# SCH_nodemcu_stepper_2023-12-21.net
KiCad netlist of a schematic drawn in EasyEDA
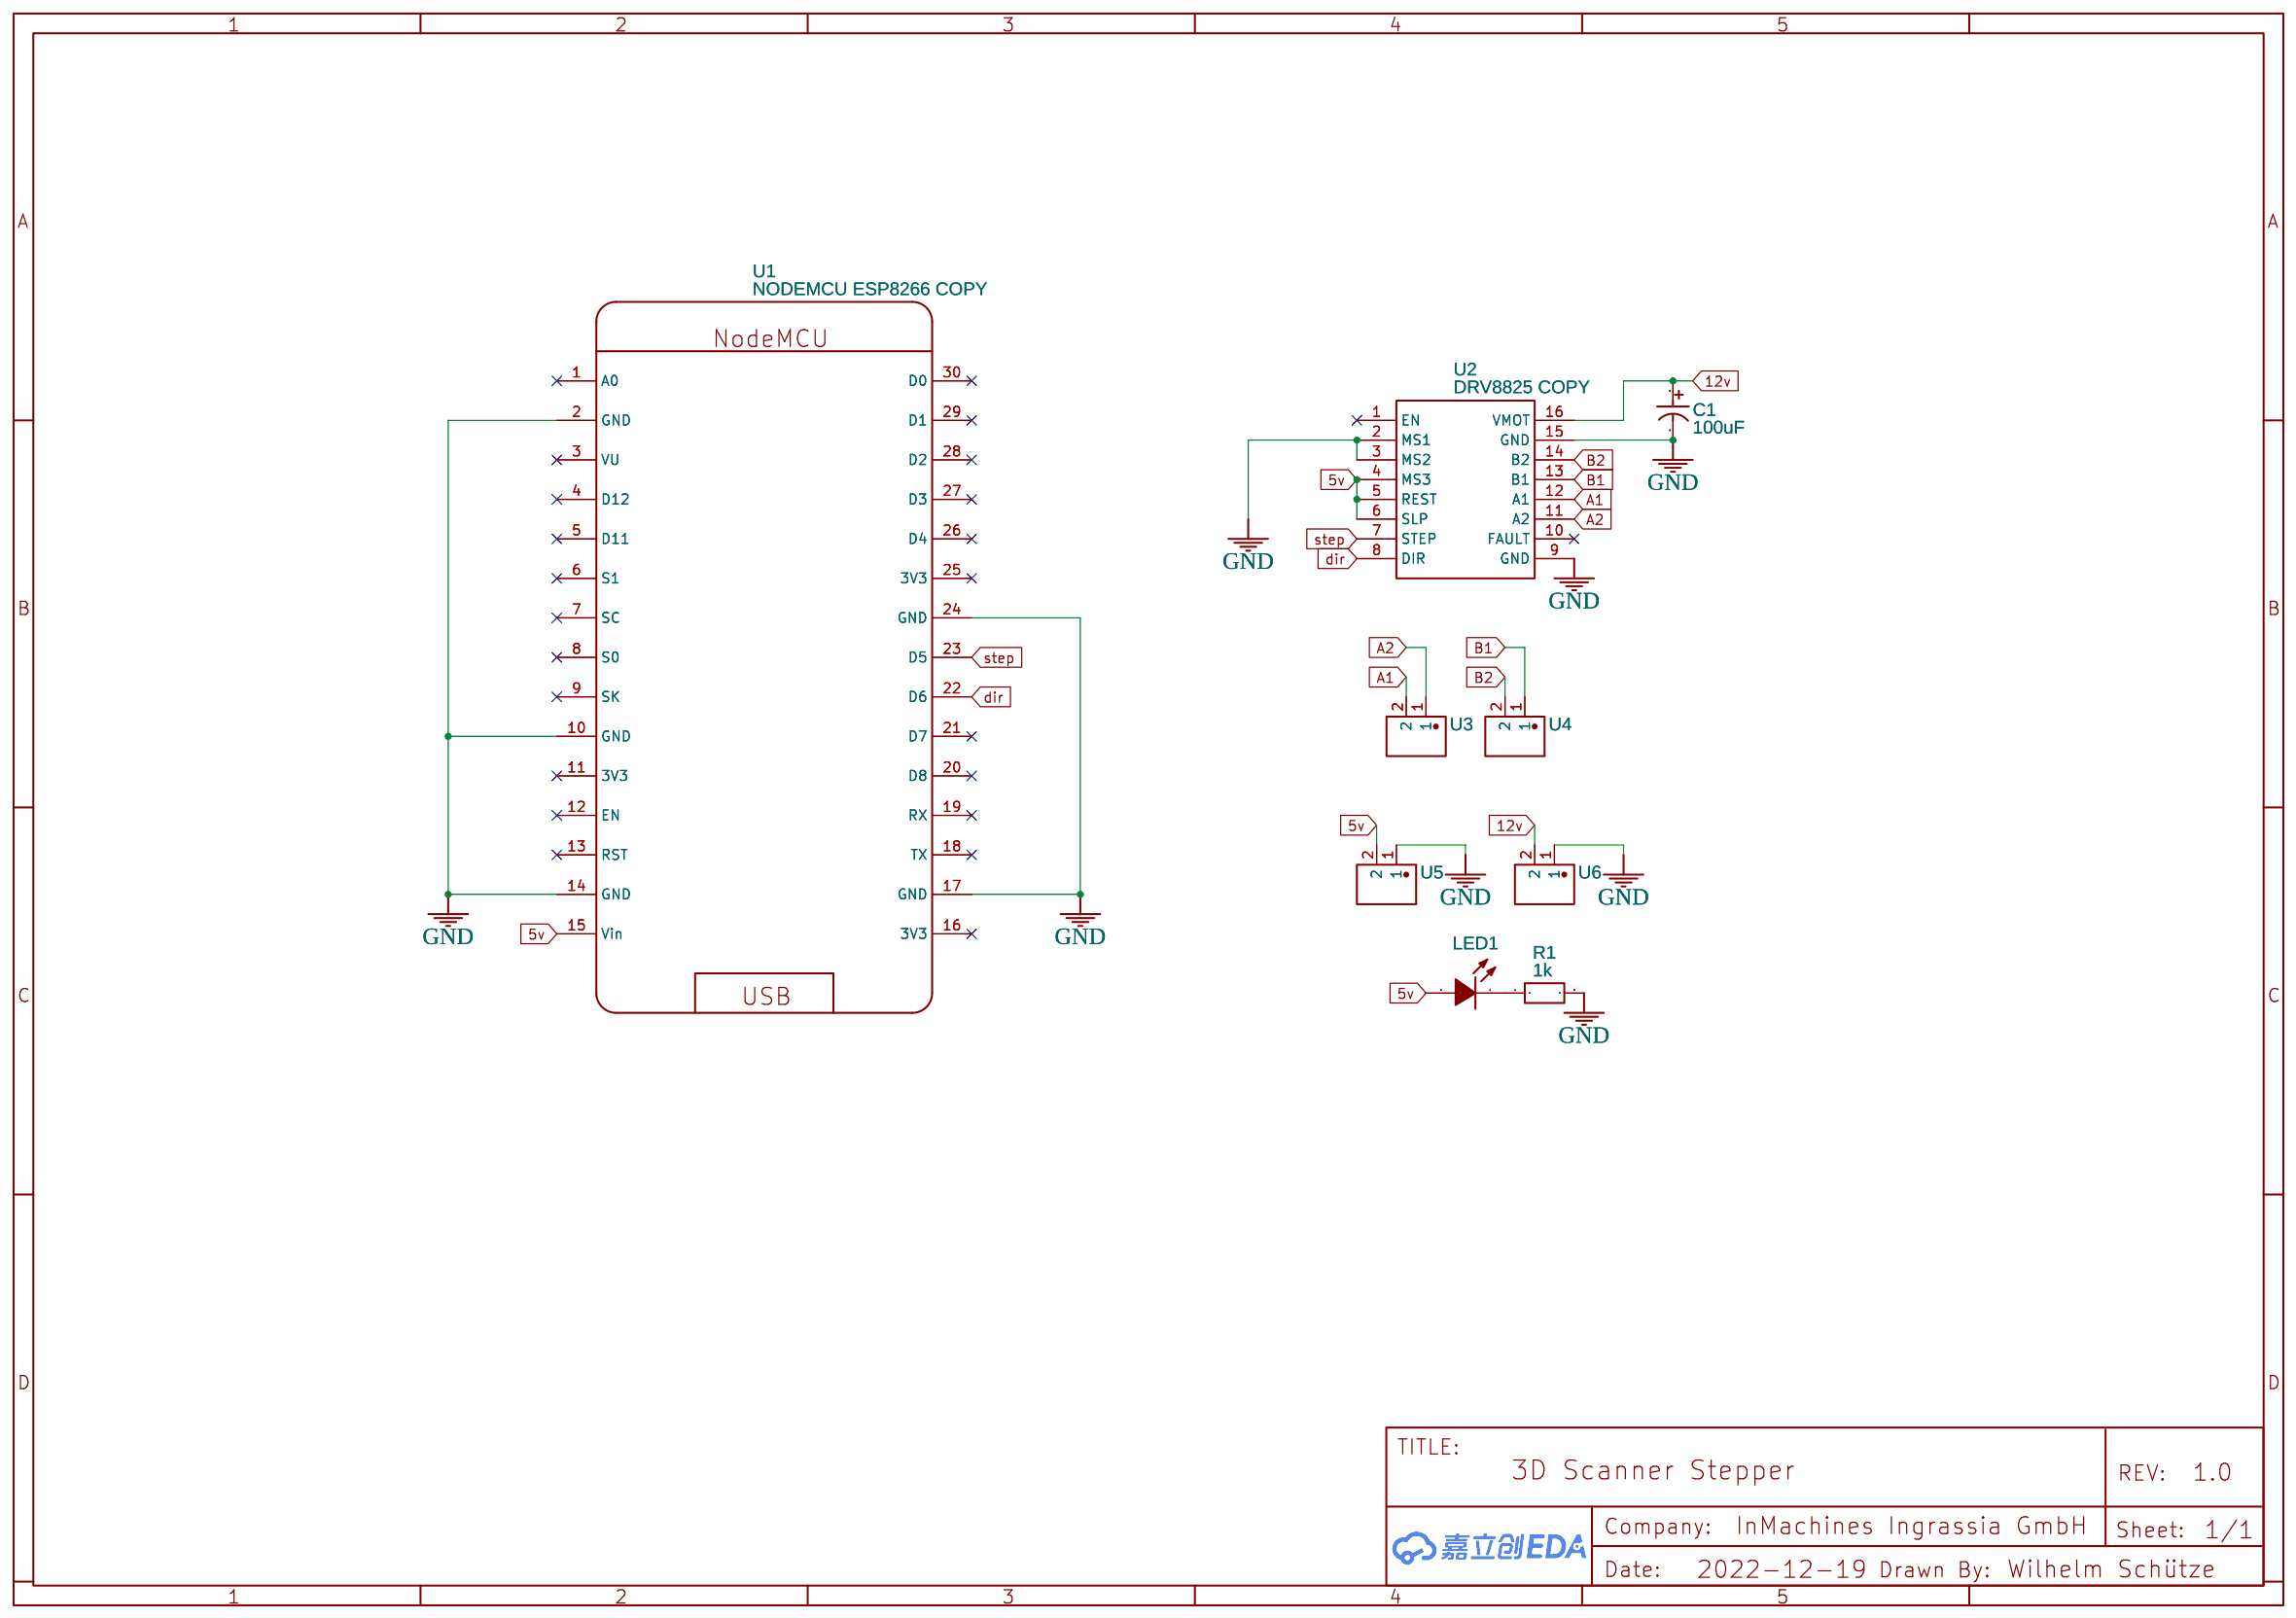
[diagram p0: schematic sheet]

(export (version "E")
  (design (tool "Eeschema 10.0.6"))
  (components
    (comp (ref "C1")
      (value "100uF")
      (fields (field (name "Manufacturer Part") "RVE1V101M0607") (field (name "Manufacturer") "ROQANG"))
      (libsource (lib "") (part "100UF-35V-KONDANSATOR"))
    )
    (comp (ref "LED1")
      (value "1206 LED Fab Lab UCAL")
      (fields (field (name "Manufacturer Part") "1206 LED") (field (name "Manufacturer") "KENTO"))
      (libsource (lib "") (part "1206 LED Fab Lab UCAL"))
    )
    (comp (ref "R1") (value "1k") (libsource (lib "") (part "R_1206_EU")))
    (comp (ref "U1") (value "NODEMCU ESP8266 COPY") (libsource (lib "") (part "NODEMCU ESP8266 COPY")))
    (comp (ref "U2") (value "DRV8825 COPY") (libsource (lib "") (part "DRV8825 COPY")))
    (comp (ref "U3")
      (value "DB128L-5.08-2P-GN-P")
      (fields (field (name "Manufacturer") "DIBO(地博电气)"))
      (libsource (lib "") (part "DB128L-5.08-2P-GN-P"))
    )
    (comp (ref "U4")
      (value "DB128L-5.08-2P-GN-P")
      (fields (field (name "Manufacturer") "DIBO(地博电气)"))
      (libsource (lib "") (part "DB128L-5.08-2P-GN-P"))
    )
    (comp (ref "U5")
      (value "DB128L-5.08-2P-GN-P")
      (fields (field (name "Manufacturer") "DIBO(地博电气)"))
      (libsource (lib "") (part "DB128L-5.08-2P-GN-P"))
    )
    (comp (ref "U6")
      (value "DB128L-5.08-2P-GN-P")
      (fields (field (name "Manufacturer") "DIBO(地博电气)"))
      (libsource (lib "") (part "DB128L-5.08-2P-GN-P"))
    )
  )
  (nets
    (net (code "1") (name "5v") (class "Default")
      (node (ref "LED1") (pin "2") (pinfunction "A_2") (pintype "unspecified"))
      (node (ref "U1") (pin "15") (pinfunction "Vin_15") (pintype "unspecified"))
      (node (ref "U2") (pin "4") (pinfunction "MS3_4") (pintype "unspecified"))
      (node (ref "U2") (pin "5") (pinfunction "REST_5") (pintype "unspecified"))
      (node (ref "U2") (pin "6") (pinfunction "SLP_6") (pintype "unspecified"))
      (node (ref "U5") (pin "2") (pinfunction "2_2") (pintype "unspecified"))
    )
    (net (code "2") (name "12v") (class "Default")
      (node (ref "C1") (pin "1") (pinfunction "1_1") (pintype "input"))
      (node (ref "U2") (pin "16") (pinfunction "VMOT_16") (pintype "unspecified"))
      (node (ref "U6") (pin "2") (pinfunction "2_2") (pintype "unspecified"))
    )
    (net (code "3") (name "A1") (class "Default")
      (node (ref "U2") (pin "12") (pinfunction "A1_12") (pintype "unspecified"))
      (node (ref "U3") (pin "2") (pinfunction "2_2") (pintype "unspecified"))
    )
    (net (code "4") (name "A2") (class "Default")
      (node (ref "U2") (pin "11") (pinfunction "A2_11") (pintype "unspecified"))
      (node (ref "U3") (pin "1") (pinfunction "1_1") (pintype "unspecified"))
    )
    (net (code "5") (name "B1") (class "Default")
      (node (ref "U2") (pin "13") (pinfunction "B1_13") (pintype "unspecified"))
      (node (ref "U4") (pin "1") (pinfunction "1_1") (pintype "unspecified"))
    )
    (net (code "6") (name "B2") (class "Default")
      (node (ref "U2") (pin "14") (pinfunction "B2_14") (pintype "unspecified"))
      (node (ref "U4") (pin "2") (pinfunction "2_2") (pintype "unspecified"))
    )
    (net (code "7") (name "GND") (class "Default")
      (node (ref "C1") (pin "2") (pinfunction "2_2") (pintype "input"))
      (node (ref "R1") (pin "2") (pinfunction "2_2") (pintype "unspecified"))
      (node (ref "U1") (pin "10") (pinfunction "GND_10") (pintype "unspecified"))
      (node (ref "U1") (pin "14") (pinfunction "GND_14") (pintype "unspecified"))
      (node (ref "U1") (pin "17") (pinfunction "GND_17") (pintype "unspecified"))
      (node (ref "U1") (pin "2") (pinfunction "GND_2") (pintype "unspecified"))
      (node (ref "U1") (pin "24") (pinfunction "GND_24") (pintype "unspecified"))
      (node (ref "U2") (pin "15") (pinfunction "GND_15") (pintype "unspecified"))
      (node (ref "U2") (pin "2") (pinfunction "MS1_2") (pintype "unspecified"))
      (node (ref "U2") (pin "3") (pinfunction "MS2_3") (pintype "unspecified"))
      (node (ref "U2") (pin "9") (pinfunction "GND_9") (pintype "unspecified"))
      (node (ref "U5") (pin "1") (pinfunction "1_1") (pintype "unspecified"))
      (node (ref "U6") (pin "1") (pinfunction "1_1") (pintype "unspecified"))
    )
    (net (code "8") (name "Net-(LED1-K)") (class "Default")
      (node (ref "LED1") (pin "1") (pinfunction "K_1") (pintype "unspecified"))
      (node (ref "R1") (pin "1") (pinfunction "1_1") (pintype "unspecified"))
    )
    (net (code "9") (name "dir") (class "Default")
      (node (ref "U1") (pin "22") (pinfunction "D6_22") (pintype "unspecified"))
      (node (ref "U2") (pin "8") (pinfunction "DIR_8") (pintype "unspecified"))
    )
    (net (code "10") (name "step") (class "Default")
      (node (ref "U1") (pin "23") (pinfunction "D5_23") (pintype "unspecified"))
      (node (ref "U2") (pin "7") (pinfunction "STEP_7") (pintype "unspecified"))
    )
    (net (code "11") (name "unconnected-(U1-3V3-Pad11)") (class "Default")
      (node (ref "U1") (pin "11") (pinfunction "3V3_11") (pintype "unspecified+no_connect"))
    )
    (net (code "12") (name "unconnected-(U1-3V3-Pad16)") (class "Default")
      (node (ref "U1") (pin "16") (pinfunction "3V3_16") (pintype "unspecified+no_connect"))
    )
    (net (code "13") (name "unconnected-(U1-3V3-Pad25)") (class "Default")
      (node (ref "U1") (pin "25") (pinfunction "3V3_25") (pintype "unspecified+no_connect"))
    )
    (net (code "14") (name "unconnected-(U1-A0-Pad1)") (class "Default")
      (node (ref "U1") (pin "1") (pinfunction "A0_1") (pintype "unspecified+no_connect"))
    )
    (net (code "15") (name "unconnected-(U1-D0-Pad30)") (class "Default")
      (node (ref "U1") (pin "30") (pinfunction "D0_30") (pintype "unspecified+no_connect"))
    )
    (net (code "16") (name "unconnected-(U1-D1-Pad29)") (class "Default")
      (node (ref "U1") (pin "29") (pinfunction "D1_29") (pintype "unspecified+no_connect"))
    )
    (net (code "17") (name "unconnected-(U1-D2-Pad28)") (class "Default")
      (node (ref "U1") (pin "28") (pinfunction "D2_28") (pintype "unspecified+no_connect"))
    )
    (net (code "18") (name "unconnected-(U1-D3-Pad27)") (class "Default")
      (node (ref "U1") (pin "27") (pinfunction "D3_27") (pintype "unspecified+no_connect"))
    )
    (net (code "19") (name "unconnected-(U1-D4-Pad26)") (class "Default")
      (node (ref "U1") (pin "26") (pinfunction "D4_26") (pintype "unspecified+no_connect"))
    )
    (net (code "20") (name "unconnected-(U1-D7-Pad21)") (class "Default")
      (node (ref "U1") (pin "21") (pinfunction "D7_21") (pintype "unspecified+no_connect"))
    )
    (net (code "21") (name "unconnected-(U1-D8-Pad20)") (class "Default")
      (node (ref "U1") (pin "20") (pinfunction "D8_20") (pintype "unspecified+no_connect"))
    )
    (net (code "22") (name "unconnected-(U1-D11-Pad5)") (class "Default")
      (node (ref "U1") (pin "5") (pinfunction "D11_5") (pintype "unspecified+no_connect"))
    )
    (net (code "23") (name "unconnected-(U1-D12-Pad4)") (class "Default")
      (node (ref "U1") (pin "4") (pinfunction "D12_4") (pintype "unspecified+no_connect"))
    )
    (net (code "24") (name "unconnected-(U1-EN-Pad12)") (class "Default")
      (node (ref "U1") (pin "12") (pinfunction "EN_12") (pintype "unspecified+no_connect"))
    )
    (net (code "25") (name "unconnected-(U1-RST-Pad13)") (class "Default")
      (node (ref "U1") (pin "13") (pinfunction "RST_13") (pintype "unspecified+no_connect"))
    )
    (net (code "26") (name "unconnected-(U1-RX-Pad19)") (class "Default")
      (node (ref "U1") (pin "19") (pinfunction "RX_19") (pintype "unspecified+no_connect"))
    )
    (net (code "27") (name "unconnected-(U1-S0-Pad8)") (class "Default")
      (node (ref "U1") (pin "8") (pinfunction "S0_8") (pintype "unspecified+no_connect"))
    )
    (net (code "28") (name "unconnected-(U1-S1-Pad6)") (class "Default")
      (node (ref "U1") (pin "6") (pinfunction "S1_6") (pintype "unspecified+no_connect"))
    )
    (net (code "29") (name "unconnected-(U1-SC-Pad7)") (class "Default")
      (node (ref "U1") (pin "7") (pinfunction "SC_7") (pintype "unspecified+no_connect"))
    )
    (net (code "30") (name "unconnected-(U1-SK-Pad9)") (class "Default")
      (node (ref "U1") (pin "9") (pinfunction "SK_9") (pintype "unspecified+no_connect"))
    )
    (net (code "31") (name "unconnected-(U1-TX-Pad18)") (class "Default")
      (node (ref "U1") (pin "18") (pinfunction "TX_18") (pintype "unspecified+no_connect"))
    )
    (net (code "32") (name "unconnected-(U1-VU-Pad3)") (class "Default")
      (node (ref "U1") (pin "3") (pinfunction "VU_3") (pintype "unspecified+no_connect"))
    )
    (net (code "33") (name "unconnected-(U2-EN-Pad1)") (class "Default")
      (node (ref "U2") (pin "1") (pinfunction "EN_1") (pintype "unspecified+no_connect"))
    )
    (net (code "34") (name "unconnected-(U2-FAULT-Pad10)") (class "Default")
      (node (ref "U2") (pin "10") (pinfunction "FAULT_10") (pintype "unspecified+no_connect"))
    )
  )
)
